# Gyroscope.net
KiCad netlist of a schematic drawn in Altium Designer
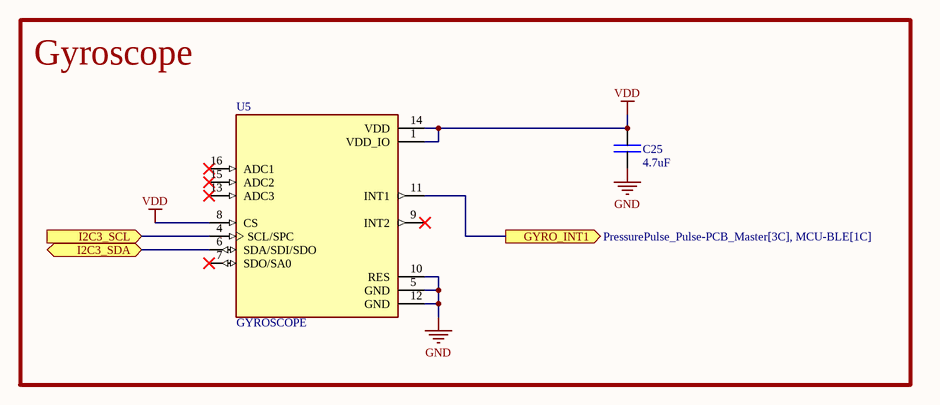
[diagram p0: Gyroscope.SchDoc]

(export (version "E")
  (design (tool "Eeschema 10.0.6"))
  (components
    (comp (ref "C25")
      (value "4.7uF")
      (footprint "PressurePulse:0402C")
      (description "Capacitor")
      (fields (field (name "Comment") "CAP"))
      (libsource (lib "PressurePulse") (part "CAP"))
    )
    (comp (ref "U5")
      (value "GYROSCOPE")
      (footprint "PressurePulse:16-VFLGA")
      (description "Accelerometer X, Y, Z Axis Â±2g, 4g, 8g, 16g 0.5Hz ~ 625Hz 16-LGA (3x3)")
      (fields (field (name "MFR") "STMicroelectronics"))
      (libsource (lib "PressurePulse") (part "GYROSCOPE"))
    )
  )
  (nets
    (net (code "1") (name "/GYRO_INT1") (class "Default")
      (node (ref "U5") (pin "11") (pinfunction "INT1_11") (pintype "output"))
    )
    (net (code "2") (name "/I2C3_SCL") (class "Default")
      (node (ref "U5") (pin "4") (pinfunction "SCL/SPC_4") (pintype "input"))
    )
    (net (code "3") (name "/I2C3_SDA") (class "Default")
      (node (ref "U5") (pin "6") (pinfunction "SDA/SDI/SDO_6") (pintype "bidirectional"))
    )
    (net (code "4") (name "GND") (class "Default")
      (node (ref "C25") (pin "1") (pinfunction "1_1") (pintype "passive"))
      (node (ref "U5") (pin "10") (pinfunction "RES_10") (pintype "passive"))
      (node (ref "U5") (pin "12") (pinfunction "GND_12") (pintype "power_in"))
      (node (ref "U5") (pin "5") (pinfunction "GND_5") (pintype "power_in"))
    )
    (net (code "5") (name "VDD") (class "Default")
      (node (ref "C25") (pin "2") (pinfunction "2_2") (pintype "passive"))
      (node (ref "U5") (pin "1") (pinfunction "VDD_IO_1") (pintype "power_in"))
      (node (ref "U5") (pin "14") (pinfunction "VDD_14") (pintype "power_in"))
      (node (ref "U5") (pin "8") (pinfunction "CS_8") (pintype "input"))
    )
    (net (code "6") (name "unconnected-(U5-ADC1-Pad16)") (class "Default")
      (node (ref "U5") (pin "16") (pinfunction "ADC1_16") (pintype "input+no_connect"))
    )
    (net (code "7") (name "unconnected-(U5-ADC2-Pad15)") (class "Default")
      (node (ref "U5") (pin "15") (pinfunction "ADC2_15") (pintype "input+no_connect"))
    )
    (net (code "8") (name "unconnected-(U5-ADC3-Pad13)") (class "Default")
      (node (ref "U5") (pin "13") (pinfunction "ADC3_13") (pintype "input+no_connect"))
    )
    (net (code "9") (name "unconnected-(U5-INT2-Pad9)") (class "Default")
      (node (ref "U5") (pin "9") (pinfunction "INT2_9") (pintype "output+no_connect"))
    )
    (net (code "10") (name "unconnected-(U5-SDO{slash}SA0-Pad7)") (class "Default")
      (node (ref "U5") (pin "7") (pinfunction "SDO/SA0_7") (pintype "bidirectional+no_connect"))
    )
  )
)
